# TOP_Sheet.net
KiCad netlist of a schematic drawn in Altium Designer
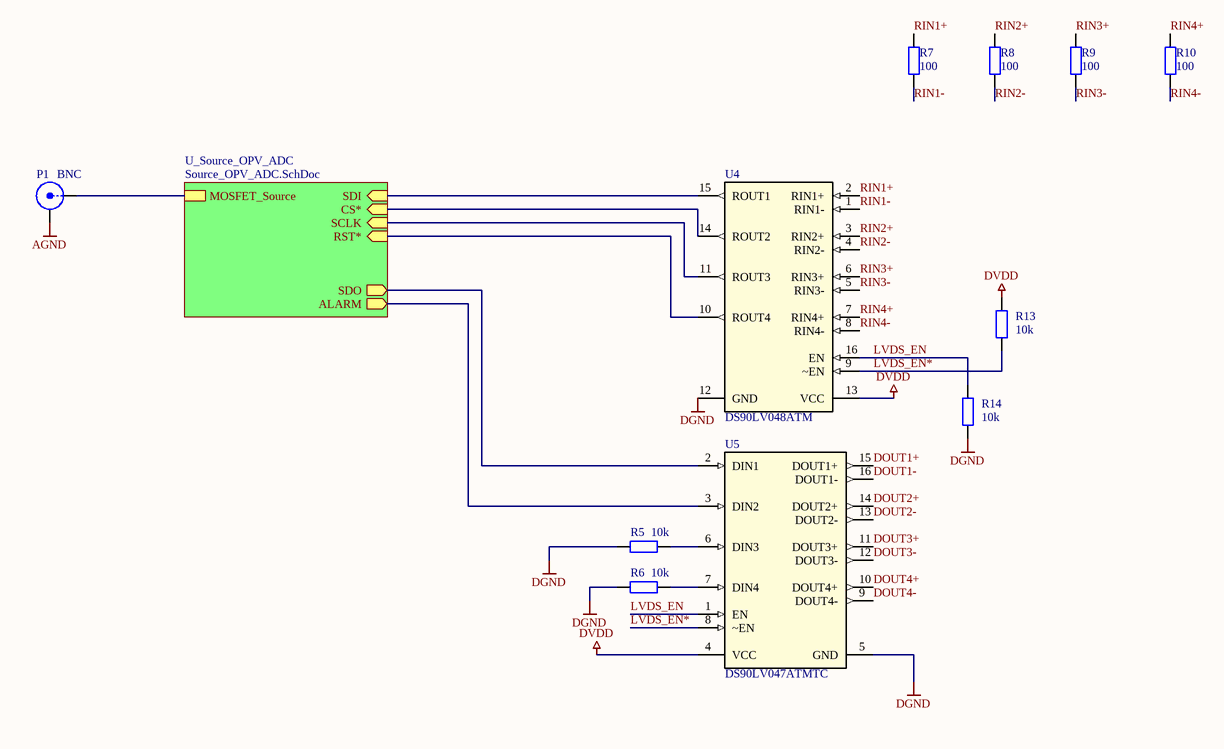
[diagram p0: TOP_Sheet.SchDoc]

(export (version "E")
  (design (tool "Eeschema 10.0.6"))
  (components
    (comp (ref "P1")
      (value "BNC")
      (footprint "BNC_RA CON")
      (description "BNC Elbow Connector")
      (fields (field (name "PUBLISHER") "Altium Limited"))
      (libsource (lib "Miscellaneous Connectors") (part "BNC"))
    )
    (comp (ref "R5")
      (value "10k")
      (footprint "C1206-KUE")
      (description "Resistor SMD")
      (fields (field (name "MANUFACTURER") "AVX") (field (name "PUBLISHER") "Altium Limited"))
      (libsource (lib "") (part "ResistorSMD_2"))
    )
    (comp (ref "R6")
      (value "10k")
      (footprint "C1206-KUE")
      (description "Resistor SMD")
      (fields (field (name "MANUFACTURER") "AVX") (field (name "PUBLISHER") "Altium Limited"))
      (libsource (lib "") (part "ResistorSMD_2"))
    )
    (comp (ref "R7")
      (value "100")
      (footprint "C1206-KUE")
      (description "Resistor SMD")
      (fields (field (name "MANUFACTURER") "AVX") (field (name "PUBLISHER") "Altium Limited"))
      (libsource (lib "ExtrapartsKUE_V01") (part "ResistorSMD"))
    )
    (comp (ref "R8")
      (value "100")
      (footprint "C1206-KUE")
      (description "Resistor SMD")
      (fields (field (name "MANUFACTURER") "AVX") (field (name "PUBLISHER") "Altium Limited"))
      (libsource (lib "ExtrapartsKUE_V01") (part "ResistorSMD"))
    )
    (comp (ref "R9")
      (value "100")
      (footprint "C1206-KUE")
      (description "Resistor SMD")
      (fields (field (name "MANUFACTURER") "AVX") (field (name "PUBLISHER") "Altium Limited"))
      (libsource (lib "ExtrapartsKUE_V01") (part "ResistorSMD"))
    )
    (comp (ref "R10")
      (value "100")
      (footprint "C1206-KUE")
      (description "Resistor SMD")
      (fields (field (name "MANUFACTURER") "AVX") (field (name "PUBLISHER") "Altium Limited"))
      (libsource (lib "ExtrapartsKUE_V01") (part "ResistorSMD"))
    )
    (comp (ref "R13")
      (value "10k")
      (footprint "C1206-KUE")
      (description "Resistor SMD")
      (fields (field (name "MANUFACTURER") "AVX") (field (name "PUBLISHER") "Altium Limited"))
      (libsource (lib "") (part "ResistorSMD_1"))
    )
    (comp (ref "R14")
      (value "10k")
      (footprint "C1206-KUE")
      (description "Resistor SMD")
      (fields (field (name "MANUFACTURER") "AVX") (field (name "PUBLISHER") "Altium Limited"))
      (libsource (lib "") (part "ResistorSMD_1"))
    )
    (comp (ref "U4")
      (value "DS90LV048ATM")
      (footprint "SOIC-16N")
      (description "400-Mbps LVDS quad high-speed differential receiver 16-SOIC -40 to 85")
      (fields
        (field (name "MANUFACTURER") "NationalSemiconductor")
        (field (name "COPYRIGHT") "Copyright (C) 2026 Ultra Librarian. All rights reserved.")
        (field (name "PUBLISHER") "AltiumLimited")
      )
      (libsource (lib "MyOwnParts") (part "DS90LV048ATM"))
    )
    (comp (ref "U5")
      (value "DS90LV047ATMTC")
      (footprint "SOIC-16N")
      (description "400-Mbps LVDS quad high-speed differential driver 16-TSSOP -40 to 85")
      (fields
        (field (name "MANUFACTURER") "NationalSemiconductor")
        (field (name "COPYRIGHT") "Copyright (C) 2025 Ultra Librarian. All rights reserved.")
        (field (name "PUBLISHER") "AltiumLimited")
      )
      (libsource (lib "MyOwnParts") (part "DS90LV047ATMTC"))
    )
  )
  (nets
    (net (code "1") (name "/ALARM") (class "Default")
      (node (ref "U5") (pin "3") (pinfunction "DIN2_3") (pintype "input"))
    )
    (net (code "2") (name "/CS*") (class "Default")
      (node (ref "U4") (pin "14") (pinfunction "ROUT2_14") (pintype "output"))
    )
    (net (code "3") (name "/DOUT1+") (class "Default")
      (node (ref "U5") (pin "15") (pinfunction "DOUT1+_15") (pintype "output"))
    )
    (net (code "4") (name "/DOUT1-") (class "Default")
      (node (ref "U5") (pin "16") (pinfunction "DOUT1-_16") (pintype "output"))
    )
    (net (code "5") (name "/DOUT2+") (class "Default")
      (node (ref "U5") (pin "14") (pinfunction "DOUT2+_14") (pintype "output"))
    )
    (net (code "6") (name "/DOUT2-") (class "Default")
      (node (ref "U5") (pin "13") (pinfunction "DOUT2-_13") (pintype "output"))
    )
    (net (code "7") (name "/DOUT3+") (class "Default")
      (node (ref "U5") (pin "11") (pinfunction "DOUT3+_11") (pintype "output"))
    )
    (net (code "8") (name "/DOUT3-") (class "Default")
      (node (ref "U5") (pin "12") (pinfunction "DOUT3-_12") (pintype "output"))
    )
    (net (code "9") (name "/DOUT4+") (class "Default")
      (node (ref "U5") (pin "10") (pinfunction "DOUT4+_10") (pintype "output"))
    )
    (net (code "10") (name "/DOUT4-") (class "Default")
      (node (ref "U5") (pin "9") (pinfunction "DOUT4-_9") (pintype "output"))
    )
    (net (code "11") (name "/LVDS_EN") (class "Default")
      (node (ref "R14") (pin "2") (pinfunction "2_2") (pintype "passive"))
      (node (ref "U4") (pin "16") (pinfunction "EN_16") (pintype "input"))
      (node (ref "U5") (pin "1") (pinfunction "EN_1") (pintype "input"))
    )
    (net (code "12") (name "/LVDS_EN*") (class "Default")
      (node (ref "R13") (pin "1") (pinfunction "1_1") (pintype "passive"))
      (node (ref "U4") (pin "9") (pinfunction "~EN_9") (pintype "input"))
      (node (ref "U5") (pin "8") (pinfunction "~EN_8") (pintype "input"))
    )
    (net (code "13") (name "/MOSFET_Source") (class "Default")
      (node (ref "P1") (pin "1") (pinfunction "X_1") (pintype "passive"))
    )
    (net (code "14") (name "/RIN1+") (class "Default")
      (node (ref "R7") (pin "1") (pinfunction "1_1") (pintype "passive"))
      (node (ref "U4") (pin "2") (pinfunction "RIN1+_2") (pintype "input"))
    )
    (net (code "15") (name "/RIN1-") (class "Default")
      (node (ref "R7") (pin "2") (pinfunction "2_2") (pintype "passive"))
      (node (ref "U4") (pin "1") (pinfunction "RIN1-_1") (pintype "input"))
    )
    (net (code "16") (name "/RIN2+") (class "Default")
      (node (ref "R8") (pin "1") (pinfunction "1_1") (pintype "passive"))
      (node (ref "U4") (pin "3") (pinfunction "RIN2+_3") (pintype "input"))
    )
    (net (code "17") (name "/RIN2-") (class "Default")
      (node (ref "R8") (pin "2") (pinfunction "2_2") (pintype "passive"))
      (node (ref "U4") (pin "4") (pinfunction "RIN2-_4") (pintype "input"))
    )
    (net (code "18") (name "/RIN3+") (class "Default")
      (node (ref "R9") (pin "1") (pinfunction "1_1") (pintype "passive"))
      (node (ref "U4") (pin "6") (pinfunction "RIN3+_6") (pintype "input"))
    )
    (net (code "19") (name "/RIN3-") (class "Default")
      (node (ref "R9") (pin "2") (pinfunction "2_2") (pintype "passive"))
      (node (ref "U4") (pin "5") (pinfunction "RIN3-_5") (pintype "input"))
    )
    (net (code "20") (name "/RIN4+") (class "Default")
      (node (ref "R10") (pin "1") (pinfunction "1_1") (pintype "passive"))
      (node (ref "U4") (pin "7") (pinfunction "RIN4+_7") (pintype "input"))
    )
    (net (code "21") (name "/RIN4-") (class "Default")
      (node (ref "R10") (pin "2") (pinfunction "2_2") (pintype "passive"))
      (node (ref "U4") (pin "8") (pinfunction "RIN4-_8") (pintype "input"))
    )
    (net (code "22") (name "/RST*") (class "Default")
      (node (ref "U4") (pin "10") (pinfunction "ROUT4_10") (pintype "output"))
    )
    (net (code "23") (name "/SCLK") (class "Default")
      (node (ref "U4") (pin "11") (pinfunction "ROUT3_11") (pintype "output"))
    )
    (net (code "24") (name "/SDI") (class "Default")
      (node (ref "U4") (pin "15") (pinfunction "ROUT1_15") (pintype "output"))
    )
    (net (code "25") (name "/SDO") (class "Default")
      (node (ref "U5") (pin "2") (pinfunction "DIN1_2") (pintype "input"))
    )
    (net (code "26") (name "AGND") (class "Default")
      (node (ref "P1") (pin "2") (pinfunction "Y_2") (pintype "passive"))
    )
    (net (code "27") (name "DGND") (class "Default")
      (node (ref "R14") (pin "1") (pinfunction "1_1") (pintype "passive"))
      (node (ref "R5") (pin "2") (pinfunction "2_2") (pintype "passive"))
      (node (ref "R6") (pin "2") (pinfunction "2_2") (pintype "passive"))
      (node (ref "U4") (pin "12") (pinfunction "GND_12") (pintype "power_in"))
      (node (ref "U5") (pin "5") (pinfunction "GND_5") (pintype "power_in"))
    )
    (net (code "28") (name "DVDD") (class "Default")
      (node (ref "R13") (pin "2") (pinfunction "2_2") (pintype "passive"))
      (node (ref "U4") (pin "13") (pinfunction "VCC_13") (pintype "power_in"))
      (node (ref "U5") (pin "4") (pinfunction "VCC_4") (pintype "power_in"))
    )
    (net (code "29") (name "Net-(U5-DIN3)") (class "Default")
      (node (ref "R5") (pin "1") (pinfunction "1_1") (pintype "passive"))
      (node (ref "U5") (pin "6") (pinfunction "DIN3_6") (pintype "input"))
    )
    (net (code "30") (name "Net-(U5-DIN4)") (class "Default")
      (node (ref "R6") (pin "1") (pinfunction "1_1") (pintype "passive"))
      (node (ref "U5") (pin "7") (pinfunction "DIN4_7") (pintype "input"))
    )
  )
)
